# Sheet1.net
KiCad netlist of a schematic drawn in Altium Designer
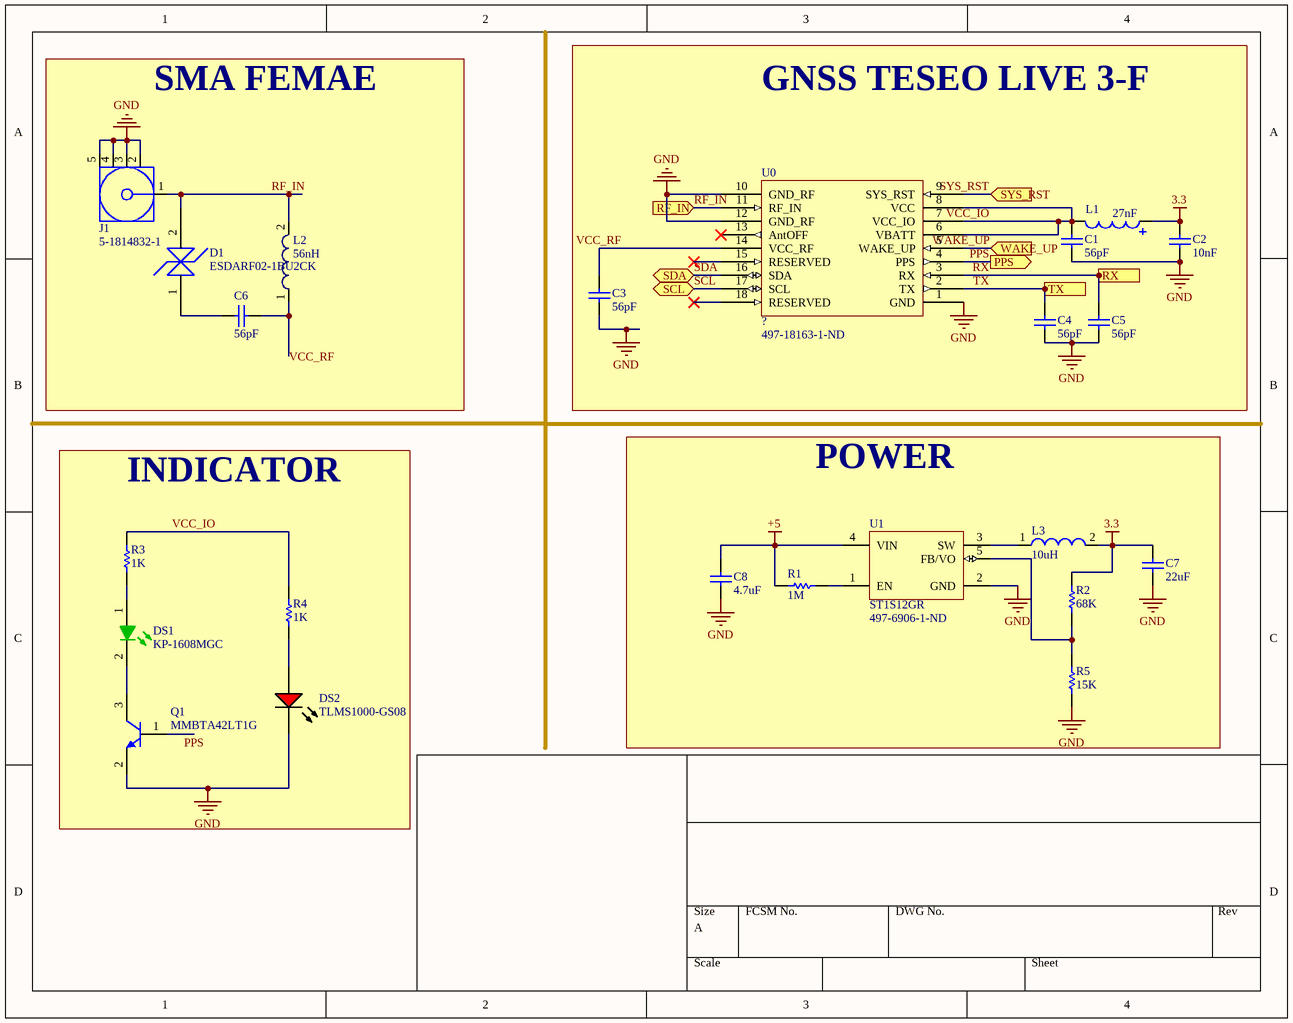
[diagram p0: Sheet1.SchDoc]

(export (version "E")
  (design (tool "Eeschema 10.0.6"))
  (components
    (comp (ref "C1")
      (value "56pF")
      (footprint "CAPC0603X33X15LL03T05")
      (description "Multilayer Ceramic Capacitors MLCC - SMD/SMT 0201 56pF 50volts C0G +/-2%")
      (fields (field (name "PART NUMBER") "GRM0335C1H560GA01D") (field (name "MANUFACTURER") "Murata"))
      (libsource (lib "Integrated_Library1") (part "CAP SMD 56pF 0201"))
    )
    (comp (ref "C2")
      (value "10nF")
      (footprint "CAPC1005X60X30LL05T10")
      (fields (field (name "MANUFACTURER") "Kemet") (field (name "PART NUMBER") "C0402C103J4RAC7867"))
      (libsource (lib "Altium Content Vault") (part "CAP"))
    )
    (comp (ref "C3")
      (value "56pF")
      (footprint "CAPC0603X33X15LL03T05")
      (description "Multilayer Ceramic Capacitors MLCC - SMD/SMT 0201 56pF 50volts C0G +/-2%")
      (fields (field (name "PART NUMBER") "GRM0335C1H560GA01D") (field (name "MANUFACTURER") "Murata"))
      (libsource (lib "Integrated_Library1") (part "CAP SMD 56pF 0201"))
    )
    (comp (ref "C4")
      (value "56pF")
      (footprint "CAPC0603X33X15LL03T05")
      (description "Multilayer Ceramic Capacitors MLCC - SMD/SMT 0201 56pF 50volts C0G +/-2%")
      (fields (field (name "PART NUMBER") "GRM0335C1H560GA01D") (field (name "MANUFACTURER") "Murata"))
      (libsource (lib "Integrated_Library1") (part "CAP SMD 56pF 0201"))
    )
    (comp (ref "C5")
      (value "56pF")
      (footprint "CAPC0603X33X15LL03T05")
      (description "Multilayer Ceramic Capacitors MLCC - SMD/SMT 0201 56pF 50volts C0G +/-2%")
      (fields (field (name "PART NUMBER") "GRM0335C1H560GA01D") (field (name "MANUFACTURER") "Murata"))
      (libsource (lib "Integrated_Library1") (part "CAP SMD 56pF 0201"))
    )
    (comp (ref "C6")
      (value "56pF")
      (footprint "CAPC0603X33X15LL03T05")
      (description "Multilayer Ceramic Capacitors MLCC - SMD/SMT 0201 56pF 50volts C0G +/-2%")
      (fields (field (name "PART NUMBER") "GRM0335C1H560GA01D") (field (name "MANUFACTURER") "Murata"))
      (libsource (lib "Integrated_Library1") (part "CAP SMD 56pF 0201"))
    )
    (comp (ref "C7")
      (value "22uF")
      (footprint "CAPC2013X145X50ML20T25")
      (fields
        (field (name "PART NUMBER") "C0805C226M9PAC7800")
        (field (name "MANUFACTURER") "Kemet")
        (field (name "TOLERANCE") "20%")
      )
      (libsource (lib "Integrated_Library1") (part "CAP SMD 22uF 0805"))
    )
    (comp (ref "C8")
      (value "4.7uF")
      (footprint "CAPC1608X90X35LL10T15")
      (description "0603 4.7 uF 25 V ±10 % Tolerance X5R SMT Multilayer Ceramic Capacitor Ceramic Capacitors 0.09620")
      (fields (field (name "PART NUMBER") "GRM188R61E475KE11D") (field (name "MANUFACTURER") "Murata"))
      (libsource (lib "Altium Content Vault") (part "CAP"))
    )
    (comp (ref "D1")
      (value "ESDARF02-1BU2CK")
      (footprint "ESDARFO2-1BU2CK")
      (description "TVS DIODE 3.6V 12V 0201")
      (libsource (lib "Integrated_Library1") (part "ESDARF02-1BU2CK"))
    )
    (comp (ref "DS1")
      (value "KP-1608MGC")
      (footprint "KING-0603LED_GREEN_V")
      (description "LED, SMT, 0603(1608), 1.1mm thickness, Green")
      (fields (field (name "MANUFACTURER") "Kingbright"))
      (libsource (lib "Altium Content Vault") (part "KING-LED-GREEN-A1K2-2"))
    )
    (comp (ref "DS2")
      (value "TLMS1000-GS08")
      (footprint "VISH-TLMS1000_V")
      (description "Low Current LED, 40 mW, 1.8 V, -40 to 100 degC, 2-Pin SMD (0603), RoHS, Tape and Reel")
      (fields (field (name "MANUFACTURER") "Vishay"))
      (libsource (lib "Altium Content Vault") (part "LED-RED-AK-2"))
    )
    (comp (ref "J1")
      (value "5-1814832-1")
      (footprint "TECO-5-1814832-1_V")
      (fields (field (name "MANUFACTURER") "TE Connectivity"))
      (libsource (lib "Altium Content Vault") (part "CN-S-4F-RF5"))
    )
    (comp (ref "L1")
      (value "27nF")
      (footprint "IND1005X55X25LL5T10")
      (description "Chip Inductor, 27 nH, 5%, 300 mA, -55 to 125 degC, 2-Pin SMD (0402), RoHS, Tape and Reel")
      (fields (field (name "TOLERANCE") "±5%") (field (name "MANUFACTURER") "Murata"))
      (libsource (lib "Integrated_Library1") (part "IND SMD 27nH 0.3A"))
    )
    (comp (ref "L2")
      (value "56nH")
      (footprint "WE-CAIR_4248")
      (description "WE-CAIR Air Coil, L=56 nH")
      (fields (field (name "MANUFACTURER") "Wuerth Elektronik") (field (name "PARTNUMBER") "744912156"))
      (libsource (lib "Altium Content Vault") (part "WE-IND-INDUCTOR-2"))
    )
    (comp (ref "L3")
      (value "10uH")
      (footprint "WE-PD2-MS")
      (description "SMD Power Inductor WE-PD2, L = 10.0 µH")
      (libsource (lib "Altium Content Vault") (part "PAS-IND-INDUCTOR-2"))
    )
    (comp (ref "Q1")
      (value "MMBTA42LT1G")
      (footprint "ONSC-SOT-23-3-318-08_V")
      (description "High Voltage Transistor, NPN Silicon, 3-Pin SOT-23, Pb-Free, Tape and Reel")
      (fields (field (name "MANUFACTURER") "On Semiconductor"))
      (libsource (lib "Altium Content Vault") (part "ONSC-NPN-B1E2C3-3"))
    )
    (comp (ref "R1")
      (value "1M")
      (footprint "RESC1005X40X25NL05T10")
      (description "RC0402JR-071ML Checked RES SMD 1M OHM 5% 1/16W 0402 Chip SMD Resistors 0.00590")
      (fields (field (name "PART NUMBER") "RC0402JR-071ML") (field (name "MANUFACTURER") "Yageo / Phycomp"))
      (libsource (lib "Integrated_Library1") (part "RES SMD 1M 0402"))
    )
    (comp (ref "R2")
      (value "68K")
      (footprint "RESC1005X37X25LL05T10")
      (description "Surface mount chip resistor 68K;\r\n1%; 1/16 W")
      (fields (field (name "PART NUMBER") "AC0402FR-0768KL") (field (name "MANUFACTURER") "Yageo"))
      (libsource (lib "Integrated_Library1") (part "RES SMD 68K 0402"))
    )
    (comp (ref "R3")
      (value "1K")
      (footprint "RESC1608X55X30LL15T15")
      (fields (field (name "PART NUMBER") "ERJ-3EKF1001V") (field (name "MANUFACTURER") "Panasonic"))
      (libsource (lib "Altium Content Vault") (part "RES"))
    )
    (comp (ref "R4")
      (value "1K")
      (footprint "RESC1608X55X30LL15T15")
      (fields (field (name "PART NUMBER") "ERJ-3EKF1001V") (field (name "MANUFACTURER") "Panasonic"))
      (libsource (lib "Altium Content Vault") (part "RES"))
    )
    (comp (ref "R5")
      (value "15K")
      (footprint "RESC1005X40X25ML05T10")
      (description "Surface mount chip resistor\r\n15 K; 1%; 1/16 W")
      (fields (field (name "MANUFACTURER") "Yageo / Phycomp") (field (name "PART NUMBER") "RC0402FR-1315KL"))
      (libsource (lib "Integrated_Library1") (part "RES SMD 15K 0402"))
    )
    (comp (ref "U0")
      (value "?")
      (footprint "TESEO LIV 3F")
      (description "GNSS MODULE")
      (fields (field (name "SUPPLIER PART NUMBER 1") "497-18163-1-ND"))
      (libsource (lib "Schlib1") (part "TESEO-LIV3F"))
    )
    (comp (ref "U1")
      (value "ST1S12GR")
      (footprint "TSOT23-5L_N")
      (fields (field (name "SUPPLIER PART NUMBER 1") "497-6906-1-ND"))
      (libsource (lib "Schlib1") (part "Syn Buck Converter"))
    )
  )
  (nets
    (net (code "1") (name "+5") (class "Default")
      (node (ref "C8") (pin "2") (pinfunction "2_2") (pintype "passive"))
      (node (ref "R1") (pin "2") (pinfunction "2_2") (pintype "passive"))
      (node (ref "U1") (pin "4") (pinfunction "VIN_4") (pintype "power_in"))
    )
    (net (code "2") (name "/PPS") (class "Default")
      (node (ref "Q1") (pin "1") (pinfunction "B_1") (pintype "passive"))
      (node (ref "U0") (pin "4") (pinfunction "PPS_4") (pintype "output"))
    )
    (net (code "3") (name "/RF_IN") (class "Default")
      (node (ref "D1") (pin "2") (pinfunction "2_2") (pintype "passive"))
      (node (ref "J1") (pin "1") (pinfunction "1_1") (pintype "passive"))
      (node (ref "L2") (pin "2") (pinfunction "2_2") (pintype "passive"))
      (node (ref "U0") (pin "11") (pinfunction "RF_IN_11") (pintype "input"))
    )
    (net (code "4") (name "/RX") (class "Default")
      (node (ref "C5") (pin "1") (pinfunction "1_1") (pintype "passive"))
      (node (ref "U0") (pin "3") (pinfunction "RX_3") (pintype "input"))
    )
    (net (code "5") (name "/SCL") (class "Default")
      (node (ref "U0") (pin "17") (pinfunction "SCL_17") (pintype "bidirectional"))
    )
    (net (code "6") (name "/SDA") (class "Default")
      (node (ref "U0") (pin "16") (pinfunction "SDA_16") (pintype "bidirectional"))
    )
    (net (code "7") (name "/SYS_RST") (class "Default")
      (node (ref "U0") (pin "9") (pinfunction "SYS_RST_9") (pintype "input"))
    )
    (net (code "8") (name "/TX") (class "Default")
      (node (ref "C4") (pin "1") (pinfunction "1_1") (pintype "passive"))
      (node (ref "U0") (pin "2") (pinfunction "TX_2") (pintype "output"))
    )
    (net (code "9") (name "/VCC_IO") (class "Default")
      (node (ref "C1") (pin "2") (pinfunction "2_2") (pintype "passive"))
      (node (ref "L1") (pin "2") (pinfunction "2_2") (pintype "passive"))
      (node (ref "R3") (pin "2") (pinfunction "2_2") (pintype "passive"))
      (node (ref "R4") (pin "2") (pinfunction "2_2") (pintype "passive"))
      (node (ref "U0") (pin "6") (pinfunction "VBATT_6") (pintype "power_in"))
      (node (ref "U0") (pin "7") (pinfunction "VCC_IO_7") (pintype "power_in"))
      (node (ref "U0") (pin "8") (pinfunction "VCC_8") (pintype "power_in"))
    )
    (net (code "10") (name "/VCC_RF") (class "Default")
      (node (ref "C3") (pin "1") (pinfunction "1_1") (pintype "passive"))
      (node (ref "C6") (pin "2") (pinfunction "2_2") (pintype "passive"))
      (node (ref "L2") (pin "1") (pinfunction "1_1") (pintype "passive"))
      (node (ref "U0") (pin "14") (pinfunction "VCC_RF_14") (pintype "power_in"))
    )
    (net (code "11") (name "/WAKE_UP") (class "Default")
      (node (ref "U0") (pin "5") (pinfunction "WAKE_UP_5") (pintype "input"))
    )
    (net (code "12") (name "3.3") (class "Default")
      (node (ref "C2") (pin "2") (pinfunction "2_2") (pintype "passive"))
      (node (ref "C7") (pin "2") (pinfunction "2_2") (pintype "passive"))
      (node (ref "L1") (pin "1") (pinfunction "1_1") (pintype "passive"))
      (node (ref "L3") (pin "2") (pinfunction "2_2") (pintype "passive"))
      (node (ref "R2") (pin "2") (pinfunction "2_2") (pintype "passive"))
    )
    (net (code "13") (name "GND") (class "Default")
      (node (ref "C1") (pin "1") (pinfunction "1_1") (pintype "passive"))
      (node (ref "C2") (pin "1") (pinfunction "1_1") (pintype "passive"))
      (node (ref "C3") (pin "2") (pinfunction "2_2") (pintype "passive"))
      (node (ref "C4") (pin "2") (pinfunction "2_2") (pintype "passive"))
      (node (ref "C5") (pin "2") (pinfunction "2_2") (pintype "passive"))
      (node (ref "C7") (pin "1") (pinfunction "1_1") (pintype "passive"))
      (node (ref "C8") (pin "1") (pinfunction "1_1") (pintype "passive"))
      (node (ref "DS2") (pin "2") (pinfunction "K_2") (pintype "passive"))
      (node (ref "J1") (pin "2") (pinfunction "2_2") (pintype "passive"))
      (node (ref "J1") (pin "3") (pinfunction "3_3") (pintype "passive"))
      (node (ref "J1") (pin "4") (pinfunction "4_4") (pintype "passive"))
      (node (ref "J1") (pin "5") (pinfunction "5_5") (pintype "passive"))
      (node (ref "Q1") (pin "2") (pinfunction "E_2") (pintype "passive"))
      (node (ref "R5") (pin "1") (pinfunction "1_1") (pintype "passive"))
      (node (ref "U0") (pin "1") (pinfunction "GND_1") (pintype "power_in"))
      (node (ref "U0") (pin "10") (pinfunction "GND_RF_10") (pintype "power_in"))
      (node (ref "U0") (pin "12") (pinfunction "GND_RF_12") (pintype "power_in"))
      (node (ref "U1") (pin "2") (pinfunction "GND_2") (pintype "power_in"))
    )
    (net (code "14") (name "Net-(C6-Pad1)") (class "Default")
      (node (ref "C6") (pin "1") (pinfunction "1_1") (pintype "passive"))
      (node (ref "D1") (pin "1") (pinfunction "1_1") (pintype "passive"))
    )
    (net (code "15") (name "Net-(DS1-A)") (class "Default")
      (node (ref "DS1") (pin "1") (pinfunction "A_1") (pintype "passive"))
      (node (ref "R3") (pin "1") (pinfunction "1_1") (pintype "passive"))
    )
    (net (code "16") (name "Net-(DS1-K)") (class "Default")
      (node (ref "DS1") (pin "2") (pinfunction "K_2") (pintype "passive"))
      (node (ref "Q1") (pin "3") (pinfunction "C_3") (pintype "passive"))
    )
    (net (code "17") (name "Net-(DS2-A)") (class "Default")
      (node (ref "DS2") (pin "1") (pinfunction "A_1") (pintype "passive"))
      (node (ref "R4") (pin "1") (pinfunction "1_1") (pintype "passive"))
    )
    (net (code "18") (name "Net-(U1-EN)") (class "Default")
      (node (ref "R1") (pin "1") (pinfunction "1_1") (pintype "passive"))
      (node (ref "U1") (pin "1") (pinfunction "EN_1") (pintype "power_in"))
    )
    (net (code "19") (name "Net-(U1-FB{slash}VO)") (class "Default")
      (node (ref "R2") (pin "1") (pinfunction "1_1") (pintype "passive"))
      (node (ref "R5") (pin "2") (pinfunction "2_2") (pintype "passive"))
      (node (ref "U1") (pin "5") (pinfunction "FB/VO_5") (pintype "bidirectional"))
    )
    (net (code "20") (name "Net-(U1-SW)") (class "Default")
      (node (ref "L3") (pin "1") (pinfunction "1_1") (pintype "passive"))
      (node (ref "U1") (pin "3") (pinfunction "SW_3") (pintype "power_in"))
    )
    (net (code "21") (name "unconnected-(U0-AntOFF-Pad13)") (class "Default")
      (node (ref "U0") (pin "13") (pinfunction "AntOFF_13") (pintype "output+no_connect"))
    )
    (net (code "22") (name "unconnected-(U0-RESERVED-Pad15)") (class "Default")
      (node (ref "U0") (pin "15") (pinfunction "RESERVED_15") (pintype "input+no_connect"))
    )
    (net (code "23") (name "unconnected-(U0-RESERVED-Pad18)") (class "Default")
      (node (ref "U0") (pin "18") (pinfunction "RESERVED_18") (pintype "input+no_connect"))
    )
  )
)
